# NeoGBP_Design_Schema.net
KiCad netlist of a schematic drawn in EasyEDA
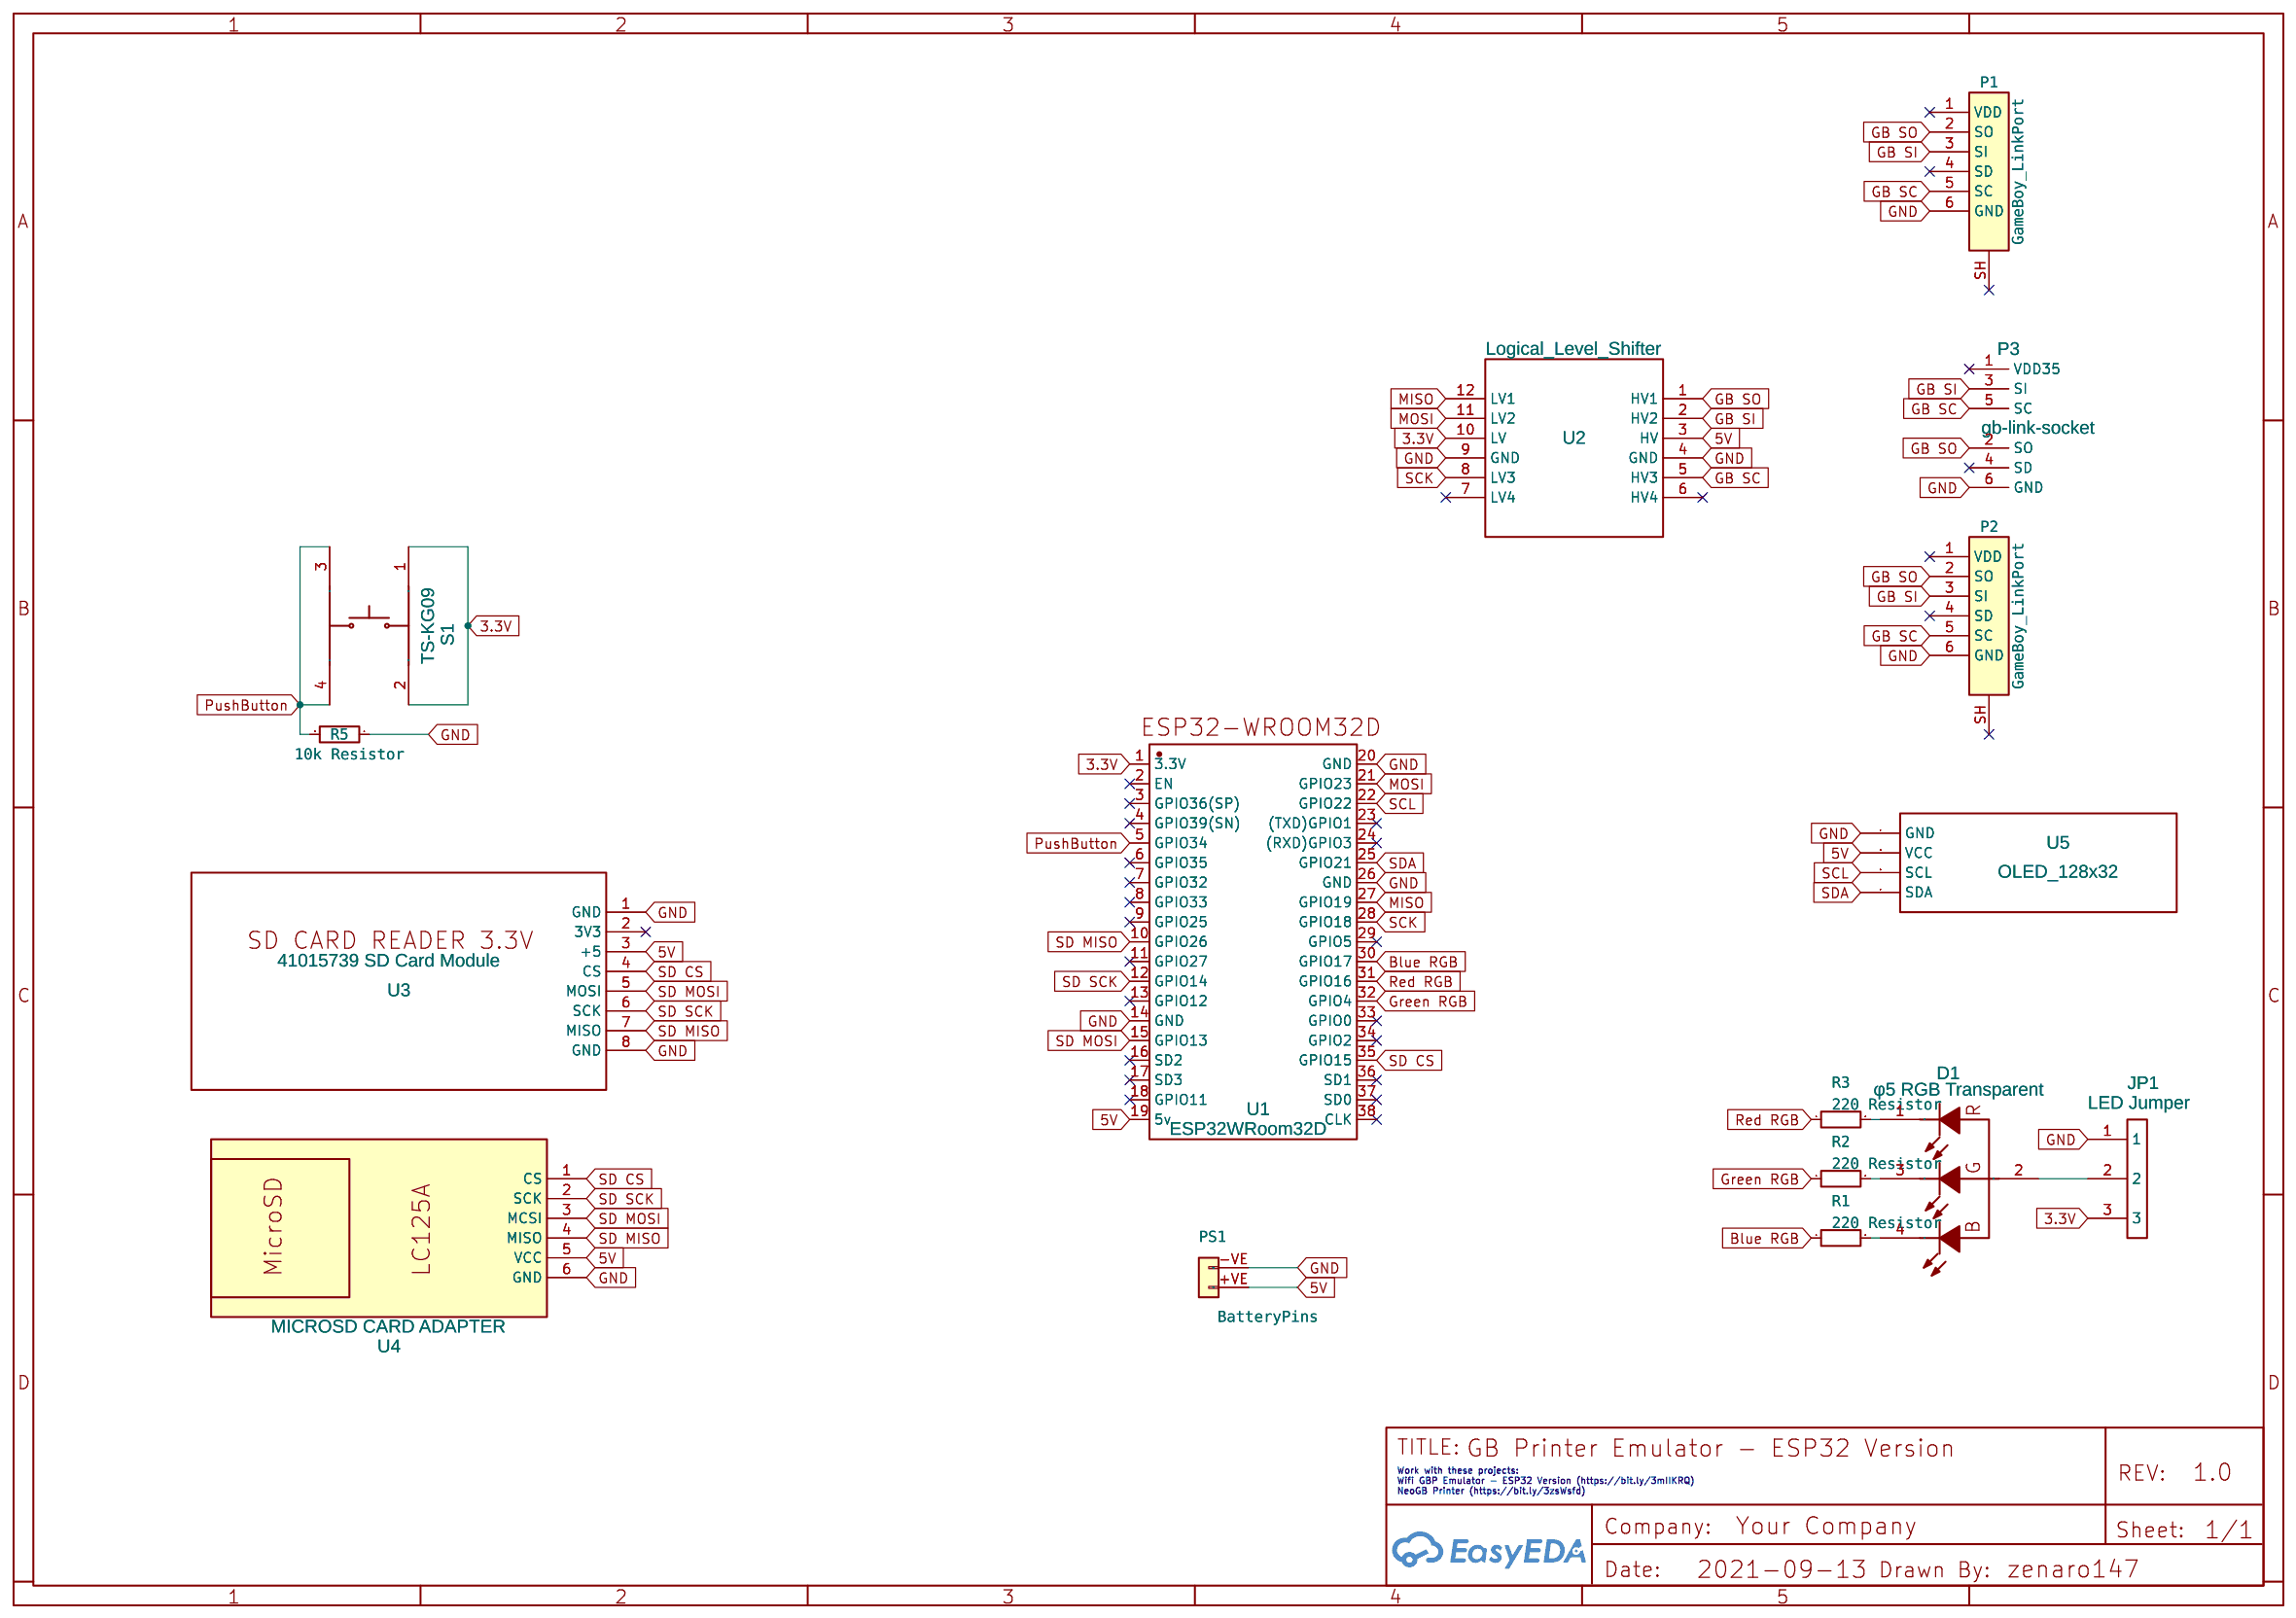
[diagram p0: schematic sheet]

(export (version "E")
  (design (tool "Eeschema 10.0.6"))
  (components
    (comp (ref "D1")
      (value "φ5 RGB Transparent")
      (fields
        (field (name "BOM_Manufacturer Part") "φ5 RGB Transparent LED")
        (field (name "BOM_Supplier Part") "C32985")
      )
      (libsource (lib "") (part "φ5 RGB Transparent"))
    )
    (comp (ref "JP1") (value "LED Jumper") (libsource (lib "") (part "Jumperpad_3")))
    (comp (ref "P1") (value "GameBoy_LinkPort") (libsource (lib "") (part "Unknown_1145_130")))
    (comp (ref "P2") (value "GameBoy_LinkPort") (libsource (lib "") (part "Unknown_1145_355")))
    (comp (ref "P3") (value "gb-link-socket") (libsource (lib "") (part "gb-link-socket")))
    (comp (ref "PS1") (value "BatteryPins") (libsource (lib "") (part "Unknown_750_685")))
    (comp (ref "R1") (value "220 Resistor") (libsource (lib "") (part "Unknown_1070_670")))
    (comp (ref "R2") (value "220 Resistor") (libsource (lib "") (part "Unknown_1070_640")))
    (comp (ref "R3") (value "220 Resistor") (libsource (lib "") (part "Unknown_1070_610")))
    (comp (ref "R5") (value "10k Resistor") (libsource (lib "") (part "Unknown_310_415")))
    (comp (ref "S1")
      (value "TS-KG09")
      (fields (field (name "BOM_Supplier Part") "C410370"))
      (libsource (lib "") (part "TS-KG09"))
    )
    (comp (ref "U1")
      (value "ESP32WRoom32D")
      (fields (field (name "BOM_Manufacturer Part") "ESp32 38pin"))
      (libsource (lib "") (part "ESP32WRoom32D"))
    )
    (comp (ref "U2")
      (value "Logical_Level_Shifter")
      (libsource (lib "") (part "Logical_Level_Shifter_Bidirectional"))
    )
    (comp (ref "U3")
      (value "41015739 SD Card Module")
      (fields (field (name "BOM_Manufacturer Part") "SD card reader IL"))
      (libsource (lib "") (part "41015739 SD Card Module"))
    )
    (comp (ref "U4")
      (value "MICROSD CARD ADAPTER")
      (fields (field (name "BOM_Supplier Part") "9453"))
      (libsource (lib "") (part "MICROSD CARD ADAPTER"))
    )
    (comp (ref "U5")
      (value "OLED_128x32")
      (fields (field (name "BOM_Manufacturer Part") "OLED 128x32"))
      (libsource (lib "") (part "OLED_128x32"))
    )
  )
  (nets
    (net (code "1") (name "3.3V") (class "Default")
      (node (ref "JP1") (pin "3") (pinfunction "3_3") (pintype "unspecified"))
      (node (ref "S1") (pin "1") (pinfunction "1_1") (pintype "unspecified"))
      (node (ref "S1") (pin "2") (pinfunction "2_2") (pintype "unspecified"))
      (node (ref "U1") (pin "1") (pinfunction "3.3V_1") (pintype "unspecified"))
      (node (ref "U2") (pin "10") (pinfunction "LV_10") (pintype "unspecified"))
    )
    (net (code "2") (name "5V") (class "Default")
      (node (ref "PS1") (pin "+VE") (pinfunction "Pin_2_+VE") (pintype "unspecified"))
      (node (ref "U1") (pin "19") (pinfunction "5v_19") (pintype "unspecified"))
      (node (ref "U2") (pin "3") (pinfunction "HV_3") (pintype "unspecified"))
      (node (ref "U3") (pin "3") (pinfunction "+5_3") (pintype "unspecified"))
      (node (ref "U4") (pin "5") (pinfunction "VCC_5") (pintype "unspecified"))
      (node (ref "U5") (pin "3") (pinfunction "VCC_3") (pintype "unspecified"))
    )
    (net (code "3") (name "Blue RGB") (class "Default")
      (node (ref "R1") (pin "1") (pintype "unspecified"))
      (node (ref "U1") (pin "30") (pinfunction "GPIO17_30") (pintype "unspecified"))
    )
    (net (code "4") (name "GB SC") (class "Default")
      (node (ref "P1") (pin "5") (pinfunction "SC_5") (pintype "unspecified"))
      (node (ref "P2") (pin "5") (pinfunction "SC_5") (pintype "unspecified"))
      (node (ref "P3") (pin "5") (pinfunction "SC_5") (pintype "input"))
      (node (ref "U2") (pin "5") (pinfunction "HV3_5") (pintype "unspecified"))
    )
    (net (code "5") (name "GB SI") (class "Default")
      (node (ref "P1") (pin "3") (pinfunction "SI_3") (pintype "unspecified"))
      (node (ref "P2") (pin "3") (pinfunction "SI_3") (pintype "unspecified"))
      (node (ref "P3") (pin "3") (pinfunction "SI_3") (pintype "input"))
      (node (ref "U2") (pin "2") (pinfunction "HV2_2") (pintype "unspecified"))
    )
    (net (code "6") (name "GB SO") (class "Default")
      (node (ref "P1") (pin "2") (pinfunction "SO_2") (pintype "unspecified"))
      (node (ref "P2") (pin "2") (pinfunction "SO_2") (pintype "unspecified"))
      (node (ref "P3") (pin "2") (pinfunction "SO_2") (pintype "input"))
      (node (ref "U2") (pin "1") (pinfunction "HV1_1") (pintype "unspecified"))
    )
    (net (code "7") (name "GND") (class "Default")
      (node (ref "JP1") (pin "1") (pinfunction "1_1") (pintype "unspecified"))
      (node (ref "P1") (pin "6") (pinfunction "GND_6") (pintype "unspecified"))
      (node (ref "P2") (pin "6") (pinfunction "GND_6") (pintype "unspecified"))
      (node (ref "P3") (pin "6") (pinfunction "GND_6") (pintype "input"))
      (node (ref "PS1") (pin "-VE") (pinfunction "Pin_1_-VE") (pintype "unspecified"))
      (node (ref "R5") (pin "1") (pintype "unspecified"))
      (node (ref "U1") (pin "14") (pinfunction "GND_14") (pintype "unspecified"))
      (node (ref "U1") (pin "20") (pinfunction "GND_20") (pintype "unspecified"))
      (node (ref "U1") (pin "26") (pinfunction "GND_26") (pintype "unspecified"))
      (node (ref "U2") (pin "4") (pinfunction "GND_4") (pintype "unspecified"))
      (node (ref "U2") (pin "9") (pinfunction "GND_9") (pintype "unspecified"))
      (node (ref "U3") (pin "1") (pinfunction "GND_1") (pintype "unspecified"))
      (node (ref "U3") (pin "8") (pinfunction "GND_8") (pintype "unspecified"))
      (node (ref "U4") (pin "6") (pinfunction "GND_6") (pintype "unspecified"))
      (node (ref "U5") (pin "4") (pinfunction "GND_4") (pintype "unspecified"))
    )
    (net (code "8") (name "Green RGB") (class "Default")
      (node (ref "R2") (pin "1") (pintype "unspecified"))
      (node (ref "U1") (pin "32") (pinfunction "GPIO4_32") (pintype "unspecified"))
    )
    (net (code "9") (name "MISO") (class "Default")
      (node (ref "U1") (pin "27") (pinfunction "GPIO19_27") (pintype "unspecified"))
      (node (ref "U2") (pin "12") (pinfunction "LV1_12") (pintype "unspecified"))
    )
    (net (code "10") (name "MOSI") (class "Default")
      (node (ref "U1") (pin "21") (pinfunction "GPIO23_21") (pintype "unspecified"))
      (node (ref "U2") (pin "11") (pinfunction "LV2_11") (pintype "unspecified"))
    )
    (net (code "11") (name "Net-(D1-CA)") (class "Default")
      (node (ref "D1") (pin "2") (pinfunction "CA_2") (pintype "unspecified"))
      (node (ref "JP1") (pin "2") (pinfunction "2_2") (pintype "unspecified"))
    )
    (net (code "12") (name "Net-(D1-KB)") (class "Default")
      (node (ref "D1") (pin "4") (pinfunction "KB_4") (pintype "unspecified"))
      (node (ref "R1") (pin "2") (pintype "unspecified"))
    )
    (net (code "13") (name "Net-(D1-KG)") (class "Default")
      (node (ref "D1") (pin "3") (pinfunction "KG_3") (pintype "unspecified"))
      (node (ref "R2") (pin "2") (pintype "unspecified"))
    )
    (net (code "14") (name "Net-(D1-KR)") (class "Default")
      (node (ref "D1") (pin "1") (pinfunction "KR_1") (pintype "unspecified"))
      (node (ref "R3") (pin "2") (pintype "unspecified"))
    )
    (net (code "15") (name "PushButton") (class "Default")
      (node (ref "R5") (pin "2") (pintype "unspecified"))
      (node (ref "S1") (pin "3") (pinfunction "3_3") (pintype "unspecified"))
      (node (ref "S1") (pin "4") (pinfunction "4_4") (pintype "unspecified"))
      (node (ref "U1") (pin "5") (pinfunction "GPIO34_5") (pintype "unspecified"))
    )
    (net (code "16") (name "Red RGB") (class "Default")
      (node (ref "R3") (pin "1") (pintype "unspecified"))
      (node (ref "U1") (pin "31") (pinfunction "GPIO16_31") (pintype "unspecified"))
    )
    (net (code "17") (name "SCK") (class "Default")
      (node (ref "U1") (pin "28") (pinfunction "GPIO18_28") (pintype "unspecified"))
      (node (ref "U2") (pin "8") (pinfunction "LV3_8") (pintype "unspecified"))
    )
    (net (code "18") (name "SCL") (class "Default")
      (node (ref "U1") (pin "22") (pinfunction "GPIO22_22") (pintype "unspecified"))
      (node (ref "U5") (pin "2") (pinfunction "SCL_2") (pintype "unspecified"))
    )
    (net (code "19") (name "SD CS") (class "Default")
      (node (ref "U1") (pin "35") (pinfunction "GPIO15_35") (pintype "unspecified"))
      (node (ref "U3") (pin "4") (pinfunction "CS_4") (pintype "unspecified"))
      (node (ref "U4") (pin "1") (pinfunction "CS_1") (pintype "unspecified"))
    )
    (net (code "20") (name "SD MISO") (class "Default")
      (node (ref "U1") (pin "10") (pinfunction "GPIO26_10") (pintype "unspecified"))
      (node (ref "U3") (pin "7") (pinfunction "MISO_7") (pintype "unspecified"))
      (node (ref "U4") (pin "4") (pinfunction "MISO_4") (pintype "unspecified"))
    )
    (net (code "21") (name "SD MOSI") (class "Default")
      (node (ref "U1") (pin "15") (pinfunction "GPIO13_15") (pintype "unspecified"))
      (node (ref "U3") (pin "5") (pinfunction "MOSI_5") (pintype "unspecified"))
      (node (ref "U4") (pin "3") (pinfunction "MCSI_3") (pintype "unspecified"))
    )
    (net (code "22") (name "SD SCK") (class "Default")
      (node (ref "U1") (pin "12") (pinfunction "GPIO14_12") (pintype "unspecified"))
      (node (ref "U3") (pin "6") (pinfunction "SCK_6") (pintype "unspecified"))
      (node (ref "U4") (pin "2") (pinfunction "SCK_2") (pintype "unspecified"))
    )
    (net (code "23") (name "SDA") (class "Default")
      (node (ref "U1") (pin "25") (pinfunction "GPIO21_25") (pintype "unspecified"))
      (node (ref "U5") (pin "1") (pinfunction "SDA_1") (pintype "unspecified"))
    )
    (net (code "24") (name "unconnected-(P1-PadSH)") (class "Default")
      (node (ref "P1") (pin "SH") (pintype "unspecified+no_connect"))
    )
    (net (code "25") (name "unconnected-(P1-SD-Pad4)") (class "Default")
      (node (ref "P1") (pin "4") (pinfunction "SD_4") (pintype "unspecified+no_connect"))
    )
    (net (code "26") (name "unconnected-(P1-VDD-Pad1)") (class "Default")
      (node (ref "P1") (pin "1") (pinfunction "VDD_1") (pintype "unspecified+no_connect"))
    )
    (net (code "27") (name "unconnected-(P2-PadSH)") (class "Default")
      (node (ref "P2") (pin "SH") (pintype "unspecified+no_connect"))
    )
    (net (code "28") (name "unconnected-(P2-SD-Pad4)") (class "Default")
      (node (ref "P2") (pin "4") (pinfunction "SD_4") (pintype "unspecified+no_connect"))
    )
    (net (code "29") (name "unconnected-(P2-VDD-Pad1)") (class "Default")
      (node (ref "P2") (pin "1") (pinfunction "VDD_1") (pintype "unspecified+no_connect"))
    )
    (net (code "30") (name "unconnected-(P3-SD-Pad4)") (class "Default")
      (node (ref "P3") (pin "4") (pinfunction "SD_4") (pintype "input+no_connect"))
    )
    (net (code "31") (name "unconnected-(P3-VDD35-Pad1)") (class "Default")
      (node (ref "P3") (pin "1") (pinfunction "VDD35_1") (pintype "input+no_connect"))
    )
    (net (code "32") (name "unconnected-(U1-(RXD)GPIO3-Pad24)") (class "Default")
      (node (ref "U1") (pin "24") (pinfunction "(RXD)GPIO3_24") (pintype "unspecified+no_connect"))
    )
    (net (code "33") (name "unconnected-(U1-(TXD)GPIO1-Pad23)") (class "Default")
      (node (ref "U1") (pin "23") (pinfunction "(TXD)GPIO1_23") (pintype "unspecified+no_connect"))
    )
    (net (code "34") (name "unconnected-(U1-CLK-Pad38)") (class "Default")
      (node (ref "U1") (pin "38") (pinfunction "CLK_38") (pintype "unspecified+no_connect"))
    )
    (net (code "35") (name "unconnected-(U1-EN-Pad2)") (class "Default")
      (node (ref "U1") (pin "2") (pinfunction "EN_2") (pintype "unspecified+no_connect"))
    )
    (net (code "36") (name "unconnected-(U1-GPIO0-Pad33)") (class "Default")
      (node (ref "U1") (pin "33") (pinfunction "GPIO0_33") (pintype "unspecified+no_connect"))
    )
    (net (code "37") (name "unconnected-(U1-GPIO2-Pad34)") (class "Default")
      (node (ref "U1") (pin "34") (pinfunction "GPIO2_34") (pintype "unspecified+no_connect"))
    )
    (net (code "38") (name "unconnected-(U1-GPIO5-Pad29)") (class "Default")
      (node (ref "U1") (pin "29") (pinfunction "GPIO5_29") (pintype "unspecified+no_connect"))
    )
    (net (code "39") (name "unconnected-(U1-GPIO11-Pad18)") (class "Default")
      (node (ref "U1") (pin "18") (pinfunction "GPIO11_18") (pintype "unspecified+no_connect"))
    )
    (net (code "40") (name "unconnected-(U1-GPIO12-Pad13)") (class "Default")
      (node (ref "U1") (pin "13") (pinfunction "GPIO12_13") (pintype "unspecified+no_connect"))
    )
    (net (code "41") (name "unconnected-(U1-GPIO25-Pad9)") (class "Default")
      (node (ref "U1") (pin "9") (pinfunction "GPIO25_9") (pintype "unspecified+no_connect"))
    )
    (net (code "42") (name "unconnected-(U1-GPIO27-Pad11)") (class "Default")
      (node (ref "U1") (pin "11") (pinfunction "GPIO27_11") (pintype "unspecified+no_connect"))
    )
    (net (code "43") (name "unconnected-(U1-GPIO32-Pad7)") (class "Default")
      (node (ref "U1") (pin "7") (pinfunction "GPIO32_7") (pintype "unspecified+no_connect"))
    )
    (net (code "44") (name "unconnected-(U1-GPIO33-Pad8)") (class "Default")
      (node (ref "U1") (pin "8") (pinfunction "GPIO33_8") (pintype "unspecified+no_connect"))
    )
    (net (code "45") (name "unconnected-(U1-GPIO35-Pad6)") (class "Default")
      (node (ref "U1") (pin "6") (pinfunction "GPIO35_6") (pintype "unspecified+no_connect"))
    )
    (net (code "46") (name "unconnected-(U1-GPIO36(SP)-Pad3)") (class "Default")
      (node (ref "U1") (pin "3") (pinfunction "GPIO36(SP)_3") (pintype "unspecified+no_connect"))
    )
    (net (code "47") (name "unconnected-(U1-GPIO39(SN)-Pad4)") (class "Default")
      (node (ref "U1") (pin "4") (pinfunction "GPIO39(SN)_4") (pintype "unspecified+no_connect"))
    )
    (net (code "48") (name "unconnected-(U1-SD0-Pad37)") (class "Default")
      (node (ref "U1") (pin "37") (pinfunction "SD0_37") (pintype "unspecified+no_connect"))
    )
    (net (code "49") (name "unconnected-(U1-SD1-Pad36)") (class "Default")
      (node (ref "U1") (pin "36") (pinfunction "SD1_36") (pintype "unspecified+no_connect"))
    )
    (net (code "50") (name "unconnected-(U1-SD2-Pad16)") (class "Default")
      (node (ref "U1") (pin "16") (pinfunction "SD2_16") (pintype "unspecified+no_connect"))
    )
    (net (code "51") (name "unconnected-(U1-SD3-Pad17)") (class "Default")
      (node (ref "U1") (pin "17") (pinfunction "SD3_17") (pintype "unspecified+no_connect"))
    )
    (net (code "52") (name "unconnected-(U2-HV4-Pad6)") (class "Default")
      (node (ref "U2") (pin "6") (pinfunction "HV4_6") (pintype "unspecified+no_connect"))
    )
    (net (code "53") (name "unconnected-(U2-LV4-Pad7)") (class "Default")
      (node (ref "U2") (pin "7") (pinfunction "LV4_7") (pintype "unspecified+no_connect"))
    )
    (net (code "54") (name "unconnected-(U3-3V3-Pad2)") (class "Default")
      (node (ref "U3") (pin "2") (pinfunction "3V3_2") (pintype "unspecified+no_connect"))
    )
  )
)
